# IRQF103C8revC.net
KiCad netlist of a schematic drawn in EAGLE
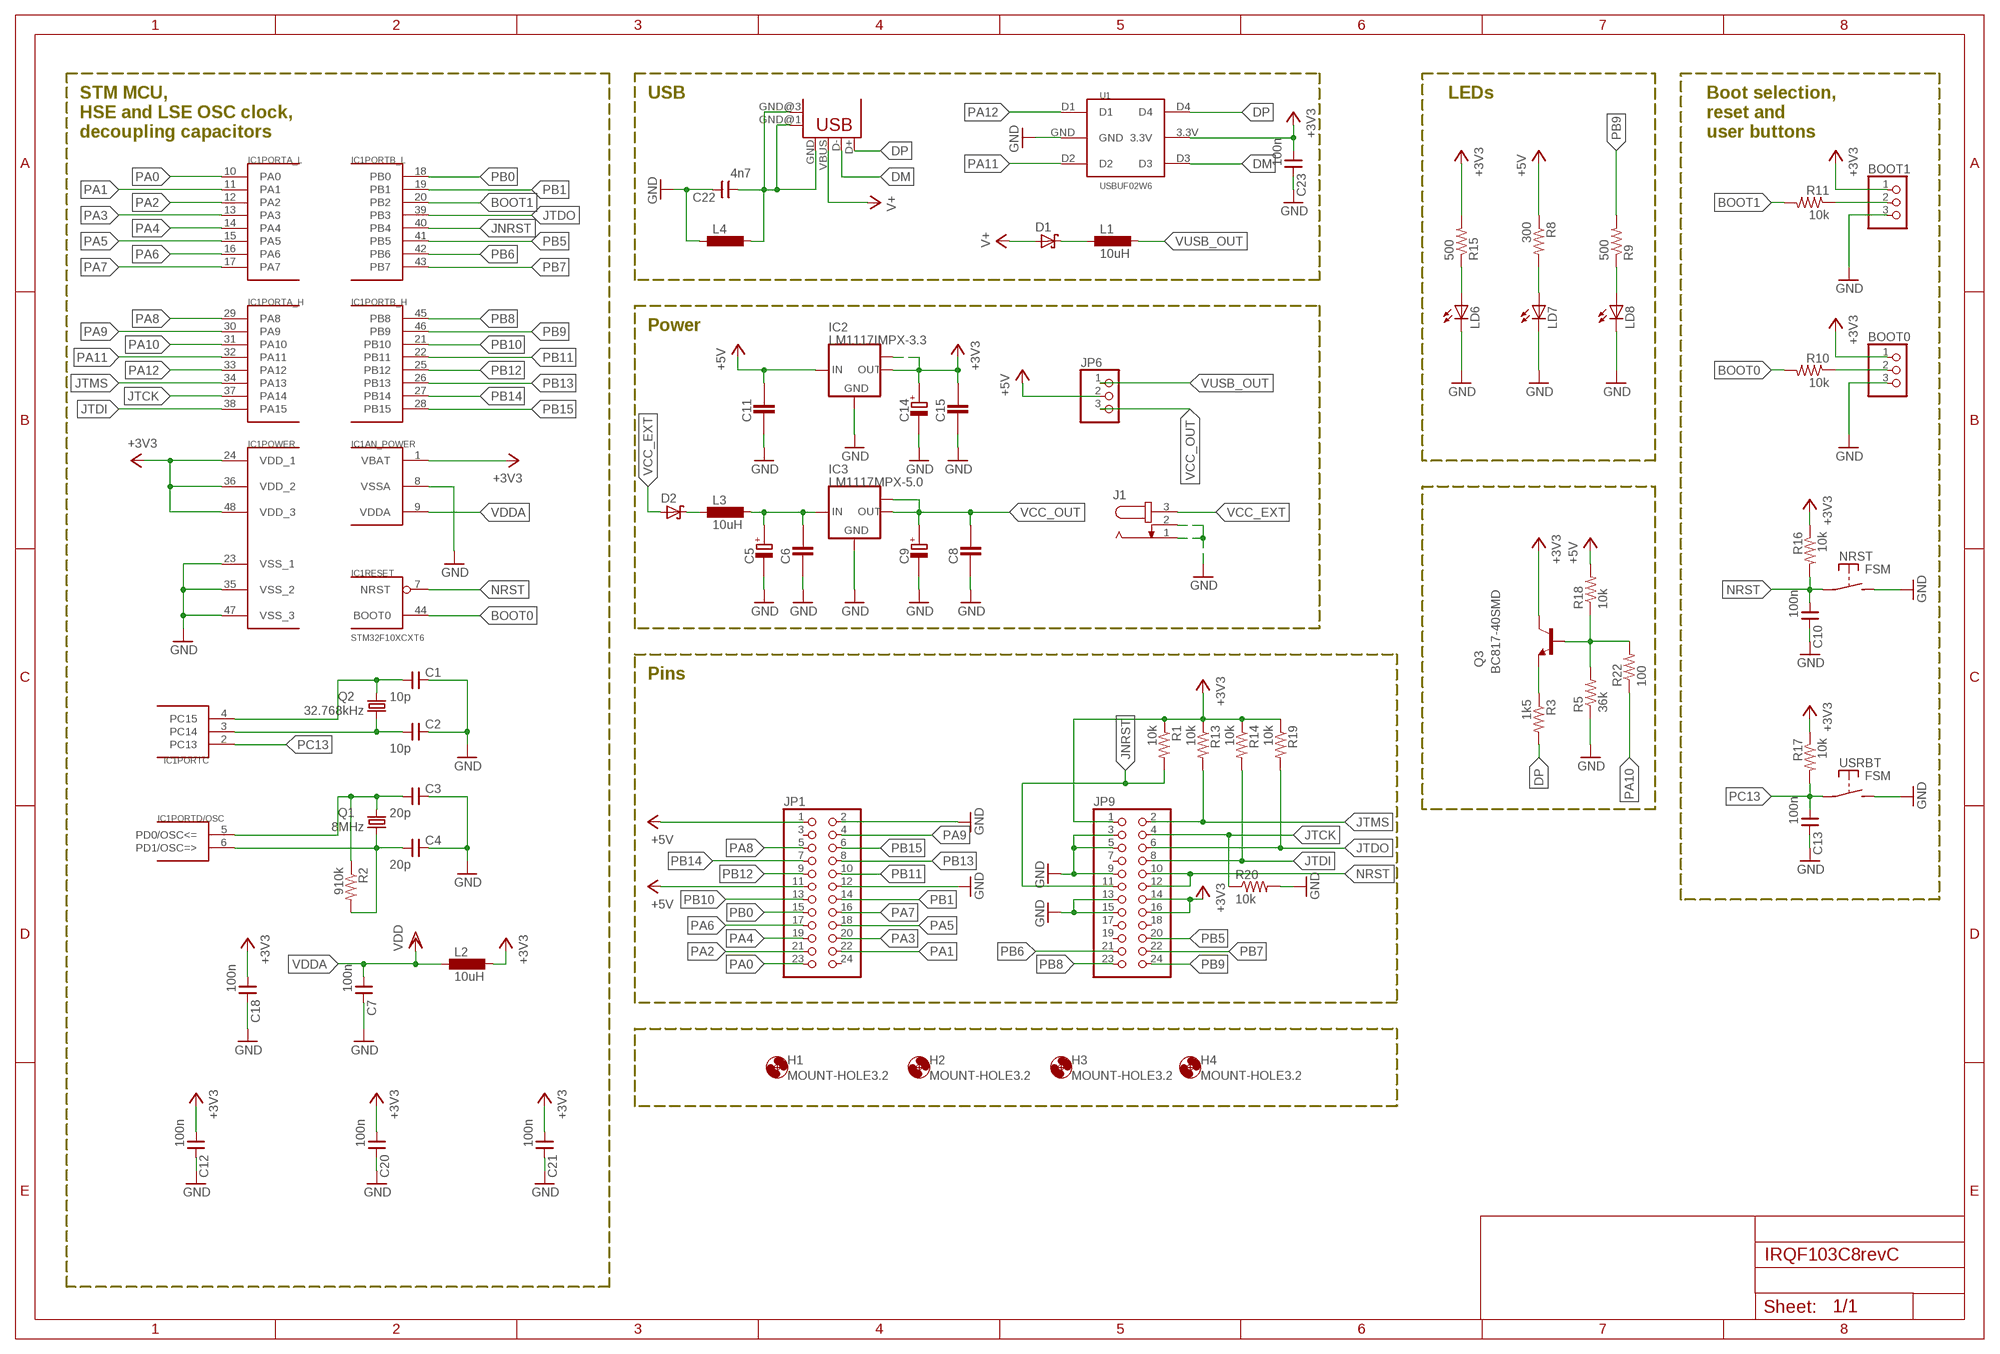
[diagram p0: schematic, sheet 1]

(export (version "E")
  (design (tool "Eeschema 10.0.6"))
  (components
    (comp (ref "BOOT0")
      (value "PINHD-1X3")
      (footprint "eagle-import:1X03")
      (libsource (lib "eagle-import") (part "PINHD-1X3"))
    )
    (comp (ref "BOOT1")
      (value "PINHD-1X3")
      (footprint "eagle-import:1X03")
      (libsource (lib "eagle-import") (part "PINHD-1X3"))
    )
    (comp (ref "C1")
      (value "10p")
      (footprint "eagle-import:0805")
      (libsource (lib "eagle-import") (part "CNP-0805"))
    )
    (comp (ref "C2")
      (value "10p")
      (footprint "eagle-import:0805")
      (libsource (lib "eagle-import") (part "CNP-0805"))
    )
    (comp (ref "C3")
      (value "20p")
      (footprint "eagle-import:0805")
      (libsource (lib "eagle-import") (part "CNP-0805"))
    )
    (comp (ref "C4")
      (value "20p")
      (footprint "eagle-import:0805")
      (libsource (lib "eagle-import") (part "CNP-0805"))
    )
    (comp (ref "C5")
      (value "POLARISED_CASE_B")
      (footprint "eagle-import:CAPAE430X540N")
      (libsource (lib "eagle-import") (part "POLARISED_CASE_B"))
    )
    (comp (ref "C6")
      (value "CAPACITOR_0805")
      (footprint "eagle-import:CAPC2012X145AN")
      (libsource (lib "eagle-import") (part "CAPACITOR_0805"))
    )
    (comp (ref "C7")
      (value "100n")
      (footprint "eagle-import:0805")
      (libsource (lib "eagle-import") (part "CNP-0805"))
    )
    (comp (ref "C8")
      (value "CAPACITOR_0805")
      (footprint "eagle-import:CAPC2012X145AN")
      (libsource (lib "eagle-import") (part "CAPACITOR_0805"))
    )
    (comp (ref "C9")
      (value "POLARISED_CASE_D")
      (footprint "eagle-import:CAPAE660X540N")
      (libsource (lib "eagle-import") (part "POLARISED_CASE_D"))
    )
    (comp (ref "C10")
      (value "100n")
      (footprint "eagle-import:0805")
      (libsource (lib "eagle-import") (part "CNP-0805"))
    )
    (comp (ref "C11")
      (value "CAPACITOR_1206")
      (footprint "eagle-import:CAPC3215X168N")
      (libsource (lib "eagle-import") (part "CAPACITOR_1206"))
    )
    (comp (ref "C12")
      (value "100n")
      (footprint "eagle-import:0805")
      (libsource (lib "eagle-import") (part "CNP-0805"))
    )
    (comp (ref "C13")
      (value "100n")
      (footprint "eagle-import:0805")
      (libsource (lib "eagle-import") (part "CNP-0805"))
    )
    (comp (ref "C14")
      (value "POLARISED_CASE_C")
      (footprint "eagle-import:CAPAE530X540N")
      (libsource (lib "eagle-import") (part "POLARISED_CASE_C"))
    )
    (comp (ref "C15")
      (value "CAPACITOR_0805")
      (footprint "eagle-import:CAPC2012X145AN")
      (libsource (lib "eagle-import") (part "CAPACITOR_0805"))
    )
    (comp (ref "C18")
      (value "100n")
      (footprint "eagle-import:0805")
      (libsource (lib "eagle-import") (part "CNP-0805"))
    )
    (comp (ref "C20")
      (value "100n")
      (footprint "eagle-import:0805")
      (libsource (lib "eagle-import") (part "CNP-0805"))
    )
    (comp (ref "C21")
      (value "100n")
      (footprint "eagle-import:0805")
      (libsource (lib "eagle-import") (part "CNP-0805"))
    )
    (comp (ref "C22")
      (value "4n7")
      (footprint "eagle-import:0805")
      (libsource (lib "eagle-import") (part "CNP-0805"))
    )
    (comp (ref "C23")
      (value "100n")
      (footprint "eagle-import:0805")
      (libsource (lib "eagle-import") (part "CNP-0805"))
    )
    (comp (ref "D1")
      (value "SCHOTTKY_SMA")
      (footprint "eagle-import:DIOM5326X292N")
      (libsource (lib "eagle-import") (part "SCHOTTKY_SMA"))
    )
    (comp (ref "D2")
      (value "SCHOTTKY_SMA")
      (footprint "eagle-import:DIOM5326X292N")
      (libsource (lib "eagle-import") (part "SCHOTTKY_SMA"))
    )
    (comp (ref "H1")
      (value "MOUNT-HOLE3.2")
      (footprint "eagle-import:3,2")
      (libsource (lib "eagle-import") (part "MOUNT-HOLE3.2"))
    )
    (comp (ref "H2")
      (value "MOUNT-HOLE3.2")
      (footprint "eagle-import:3,2")
      (libsource (lib "eagle-import") (part "MOUNT-HOLE3.2"))
    )
    (comp (ref "H3")
      (value "MOUNT-HOLE3.2")
      (footprint "eagle-import:3,2")
      (libsource (lib "eagle-import") (part "MOUNT-HOLE3.2"))
    )
    (comp (ref "H4")
      (value "MOUNT-HOLE3.2")
      (footprint "eagle-import:3,2")
      (libsource (lib "eagle-import") (part "MOUNT-HOLE3.2"))
    )
    (comp (ref "IC1")
      (value "STM32F10XCXT6")
      (footprint "eagle-import:TQFP48")
      (libsource (lib "eagle-import") (part "STM32F10XCXT6"))
    )
    (comp (ref "IC2")
      (value "LM1117IMPX-3.3")
      (footprint "eagle-import:SOT223")
      (libsource (lib "eagle-import") (part "LM1117IMPX-3.3"))
    )
    (comp (ref "IC3")
      (value "LM1117MPX-5.0")
      (footprint "eagle-import:SOT223")
      (libsource (lib "eagle-import") (part "LM1117MPX-5.0"))
    )
    (comp (ref "J1")
      (value "JACK-PLUG1")
      (footprint "eagle-import:SPC4078")
      (libsource (lib "eagle-import") (part "JACK-PLUG1"))
    )
    (comp (ref "JP1")
      (value "PINHD-2X12")
      (footprint "eagle-import:2X12")
      (libsource (lib "eagle-import") (part "PINHD-2X12"))
    )
    (comp (ref "JP6")
      (value "PINHD-1X3")
      (footprint "eagle-import:1X03")
      (libsource (lib "eagle-import") (part "PINHD-1X3"))
    )
    (comp (ref "JP9")
      (value "PINHD-2X12")
      (footprint "eagle-import:2X12")
      (libsource (lib "eagle-import") (part "PINHD-2X12"))
    )
    (comp (ref "L1")
      (value "10uH")
      (footprint "eagle-import:INDC1608X95N")
      (libsource (lib "eagle-import") (part "INDUCTOR_0603"))
    )
    (comp (ref "L2")
      (value "10uH")
      (footprint "eagle-import:INDC1608X95N")
      (libsource (lib "eagle-import") (part "INDUCTOR_0603"))
    )
    (comp (ref "L3")
      (value "10uH")
      (footprint "eagle-import:INDC1608X95N")
      (libsource (lib "eagle-import") (part "INDUCTOR_0603"))
    )
    (comp (ref "L4")
      (value "INDUCTOR_0603")
      (footprint "eagle-import:INDC1608X95N")
      (libsource (lib "eagle-import") (part "INDUCTOR_0603"))
    )
    (comp (ref "LD6")
      (value "LEDCHIPLED_0805")
      (footprint "eagle-import:CHIPLED_0805")
      (libsource (lib "eagle-import") (part "LEDCHIPLED_0805"))
    )
    (comp (ref "LD7")
      (value "LEDCHIPLED_0805")
      (footprint "eagle-import:CHIPLED_0805")
      (libsource (lib "eagle-import") (part "LEDCHIPLED_0805"))
    )
    (comp (ref "LD8")
      (value "LEDCHIPLED_0805")
      (footprint "eagle-import:CHIPLED_0805")
      (libsource (lib "eagle-import") (part "LEDCHIPLED_0805"))
    )
    (comp (ref "NRST")
      (value "FSM")
      (footprint "eagle-import:FSM")
      (libsource (lib "eagle-import") (part "FSM"))
    )
    (comp (ref "Q1")
      (value "8MHz")
      (footprint "eagle-import:HC49_S")
      (libsource (lib "eagle-import") (part "CRYTALHC49S"))
    )
    (comp (ref "Q2")
      (value "32.768kHz")
      (footprint "eagle-import:TC26H")
      (libsource (lib "eagle-import") (part "CRYTALTC26H"))
    )
    (comp (ref "Q3")
      (value "BC817-40SMD")
      (footprint "eagle-import:SOT23-BEC")
      (libsource (lib "eagle-import") (part "BC817SMD-40"))
    )
    (comp (ref "R1")
      (value "10k")
      (footprint "eagle-import:M0805")
      (libsource (lib "eagle-import") (part "R-US_M0805"))
    )
    (comp (ref "R2")
      (value "910k")
      (footprint "eagle-import:M0805")
      (libsource (lib "eagle-import") (part "R-US_M0805"))
    )
    (comp (ref "R3")
      (value "1k5")
      (footprint "eagle-import:M0805")
      (libsource (lib "eagle-import") (part "R-US_M0805"))
    )
    (comp (ref "R5")
      (value "36k")
      (footprint "eagle-import:M0805")
      (libsource (lib "eagle-import") (part "R-US_M0805"))
    )
    (comp (ref "R8")
      (value "300")
      (footprint "eagle-import:M0805")
      (libsource (lib "eagle-import") (part "R-US_M0805"))
    )
    (comp (ref "R9")
      (value "500")
      (footprint "eagle-import:M0805")
      (libsource (lib "eagle-import") (part "R-US_M0805"))
    )
    (comp (ref "R10")
      (value "10k")
      (footprint "eagle-import:M0805")
      (libsource (lib "eagle-import") (part "R-US_M0805"))
    )
    (comp (ref "R11")
      (value "10k")
      (footprint "eagle-import:M0805")
      (libsource (lib "eagle-import") (part "R-US_M0805"))
    )
    (comp (ref "R13")
      (value "10k")
      (footprint "eagle-import:M0805")
      (libsource (lib "eagle-import") (part "R-US_M0805"))
    )
    (comp (ref "R14")
      (value "10k")
      (footprint "eagle-import:M0805")
      (libsource (lib "eagle-import") (part "R-US_M0805"))
    )
    (comp (ref "R15")
      (value "500")
      (footprint "eagle-import:M0805")
      (libsource (lib "eagle-import") (part "R-US_M0805"))
    )
    (comp (ref "R16")
      (value "10k")
      (footprint "eagle-import:M0805")
      (libsource (lib "eagle-import") (part "R-US_M0805"))
    )
    (comp (ref "R17")
      (value "10k")
      (footprint "eagle-import:M0805")
      (libsource (lib "eagle-import") (part "R-US_M0805"))
    )
    (comp (ref "R18")
      (value "10k")
      (footprint "eagle-import:M0805")
      (libsource (lib "eagle-import") (part "R-US_M0805"))
    )
    (comp (ref "R19")
      (value "10k")
      (footprint "eagle-import:M0805")
      (libsource (lib "eagle-import") (part "R-US_M0805"))
    )
    (comp (ref "R20")
      (value "10k")
      (footprint "eagle-import:M0805")
      (libsource (lib "eagle-import") (part "R-US_M0805"))
    )
    (comp (ref "R22")
      (value "100")
      (footprint "eagle-import:M0805")
      (libsource (lib "eagle-import") (part "R-US_M0805"))
    )
    (comp (ref "U1")
      (value "USBUF02W6")
      (footprint "eagle-import:SOT23-6L")
      (libsource (lib "eagle-import") (part "USBUF02W6"))
    )
    (comp (ref "USB1")
      (value "USB-MB-S")
      (footprint "eagle-import:USB-MB-S")
      (libsource (lib "eagle-import") (part "USB-MB-S"))
    )
    (comp (ref "USRBT")
      (value "FSM")
      (footprint "eagle-import:FSM")
      (libsource (lib "eagle-import") (part "FSM"))
    )
  )
  (nets
    (net (code "1") (name "+3V3") (class "Default")
      (node (ref "BOOT0") (pin "1") (pinfunction "1_1") (pintype "passive"))
      (node (ref "BOOT1") (pin "1") (pinfunction "1_1") (pintype "passive"))
      (node (ref "C12") (pin "1") (pinfunction "1_1") (pintype "passive"))
      (node (ref "C14") (pin "+") (pinfunction "+_+") (pintype "passive"))
      (node (ref "C15") (pin "2") (pinfunction "2_2") (pintype "passive"))
      (node (ref "C18") (pin "1") (pinfunction "1_1") (pintype "passive"))
      (node (ref "C20") (pin "1") (pinfunction "1_1") (pintype "passive"))
      (node (ref "C21") (pin "1") (pinfunction "1_1") (pintype "passive"))
      (node (ref "C23") (pin "1") (pinfunction "1_1") (pintype "passive"))
      (node (ref "IC1") (pin "1") (pinfunction "VBAT_1") (pintype "power_in"))
      (node (ref "IC1") (pin "24") (pinfunction "VDD_1_24") (pintype "power_in"))
      (node (ref "IC1") (pin "36") (pinfunction "VDD_2_36") (pintype "power_in"))
      (node (ref "IC1") (pin "48") (pinfunction "VDD_3_48") (pintype "power_in"))
      (node (ref "IC2") (pin "2") (pinfunction "OUT_2") (pintype "passive"))
      (node (ref "IC2") (pin "TAB") (pinfunction "OUT1_TAB") (pintype "passive"))
      (node (ref "JP9") (pin "1") (pinfunction "1_1") (pintype "passive"))
      (node (ref "JP9") (pin "14") (pinfunction "14_14") (pintype "passive"))
      (node (ref "JP9") (pin "16") (pinfunction "16_16") (pintype "passive"))
      (node (ref "L2") (pin "2") (pinfunction "2_2") (pintype "passive"))
      (node (ref "Q3") (pin "C") (pinfunction "C_C") (pintype "passive"))
      (node (ref "R1") (pin "1") (pinfunction "1_1") (pintype "passive"))
      (node (ref "R13") (pin "1") (pinfunction "1_1") (pintype "passive"))
      (node (ref "R14") (pin "1") (pinfunction "1_1") (pintype "passive"))
      (node (ref "R15") (pin "2") (pinfunction "2_2") (pintype "passive"))
      (node (ref "R16") (pin "1") (pinfunction "1_1") (pintype "passive"))
      (node (ref "R17") (pin "1") (pinfunction "1_1") (pintype "passive"))
      (node (ref "R19") (pin "1") (pinfunction "1_1") (pintype "passive"))
      (node (ref "U1") (pin "3.3V") (pinfunction "3.3V_3.3V") (pintype "bidirectional"))
    )
    (net (code "2") (name "+5V") (class "Default")
      (node (ref "C11") (pin "2") (pinfunction "2_2") (pintype "passive"))
      (node (ref "IC2") (pin "3") (pinfunction "IN_3") (pintype "input"))
      (node (ref "JP1") (pin "1") (pinfunction "1_1") (pintype "passive"))
      (node (ref "JP1") (pin "11") (pinfunction "11_11") (pintype "passive"))
      (node (ref "JP6") (pin "2") (pinfunction "2_2") (pintype "passive"))
      (node (ref "R18") (pin "2") (pinfunction "2_2") (pintype "passive"))
      (node (ref "R8") (pin "1") (pinfunction "1_1") (pintype "passive"))
    )
    (net (code "3") (name "BOOT0") (class "Default")
      (node (ref "IC1") (pin "44") (pinfunction "BOOT0_44") (pintype "input"))
      (node (ref "R10") (pin "2") (pinfunction "2_2") (pintype "passive"))
    )
    (net (code "4") (name "BOOT1") (class "Default")
      (node (ref "IC1") (pin "20") (pinfunction "PB2_20") (pintype "bidirectional"))
      (node (ref "R11") (pin "2") (pinfunction "2_2") (pintype "passive"))
    )
    (net (code "5") (name "DM") (class "Default")
      (node (ref "U1") (pin "D3") (pinfunction "D3_D3") (pintype "bidirectional"))
      (node (ref "USB1") (pin "D-") (pinfunction "D-_D-") (pintype "bidirectional"))
    )
    (net (code "6") (name "DP") (class "Default")
      (node (ref "R3") (pin "2") (pinfunction "2_2") (pintype "passive"))
      (node (ref "U1") (pin "D4") (pinfunction "D4_D4") (pintype "bidirectional"))
      (node (ref "USB1") (pin "D+") (pinfunction "D+_D+") (pintype "bidirectional"))
    )
    (net (code "7") (name "GND") (class "Default")
      (node (ref "BOOT0") (pin "3") (pinfunction "3_3") (pintype "passive"))
      (node (ref "BOOT1") (pin "3") (pinfunction "3_3") (pintype "passive"))
      (node (ref "C1") (pin "2") (pinfunction "2_2") (pintype "passive"))
      (node (ref "C10") (pin "2") (pinfunction "2_2") (pintype "passive"))
      (node (ref "C11") (pin "1") (pinfunction "1_1") (pintype "passive"))
      (node (ref "C12") (pin "2") (pinfunction "2_2") (pintype "passive"))
      (node (ref "C13") (pin "2") (pinfunction "2_2") (pintype "passive"))
      (node (ref "C14") (pin "-") (pinfunction "-_-") (pintype "passive"))
      (node (ref "C15") (pin "1") (pinfunction "1_1") (pintype "passive"))
      (node (ref "C18") (pin "2") (pinfunction "2_2") (pintype "passive"))
      (node (ref "C2") (pin "2") (pinfunction "2_2") (pintype "passive"))
      (node (ref "C20") (pin "2") (pinfunction "2_2") (pintype "passive"))
      (node (ref "C21") (pin "2") (pinfunction "2_2") (pintype "passive"))
      (node (ref "C22") (pin "2") (pinfunction "2_2") (pintype "passive"))
      (node (ref "C23") (pin "2") (pinfunction "2_2") (pintype "passive"))
      (node (ref "C3") (pin "2") (pinfunction "2_2") (pintype "passive"))
      (node (ref "C4") (pin "2") (pinfunction "2_2") (pintype "passive"))
      (node (ref "C5") (pin "-") (pinfunction "-_-") (pintype "passive"))
      (node (ref "C6") (pin "1") (pinfunction "1_1") (pintype "passive"))
      (node (ref "C7") (pin "2") (pinfunction "2_2") (pintype "passive"))
      (node (ref "C8") (pin "1") (pinfunction "1_1") (pintype "passive"))
      (node (ref "C9") (pin "-") (pinfunction "-_-") (pintype "passive"))
      (node (ref "IC1") (pin "23") (pinfunction "VSS_1_23") (pintype "power_in"))
      (node (ref "IC1") (pin "35") (pinfunction "VSS_2_35") (pintype "power_in"))
      (node (ref "IC1") (pin "47") (pinfunction "VSS_3_47") (pintype "power_in"))
      (node (ref "IC1") (pin "8") (pinfunction "VSSA_8") (pintype "power_in"))
      (node (ref "IC2") (pin "1") (pinfunction "GND_1") (pintype "input"))
      (node (ref "IC3") (pin "1") (pinfunction "GND_1") (pintype "input"))
      (node (ref "J1") (pin "1") (pinfunction "1_1") (pintype "passive"))
      (node (ref "J1") (pin "2") (pinfunction "2_2") (pintype "passive"))
      (node (ref "JP1") (pin "12") (pinfunction "12_12") (pintype "passive"))
      (node (ref "JP1") (pin "2") (pinfunction "2_2") (pintype "passive"))
      (node (ref "JP9") (pin "13") (pinfunction "13_13") (pintype "passive"))
      (node (ref "JP9") (pin "15") (pinfunction "15_15") (pintype "passive"))
      (node (ref "JP9") (pin "3") (pinfunction "3_3") (pintype "passive"))
      (node (ref "JP9") (pin "5") (pinfunction "5_5") (pintype "passive"))
      (node (ref "JP9") (pin "9") (pinfunction "9_9") (pintype "passive"))
      (node (ref "L4") (pin "1") (pinfunction "1_1") (pintype "passive"))
      (node (ref "LD6") (pin "C") (pinfunction "C_C") (pintype "passive"))
      (node (ref "LD7") (pin "C") (pinfunction "C_C") (pintype "passive"))
      (node (ref "LD8") (pin "C") (pinfunction "C_C") (pintype "passive"))
      (node (ref "NRST") (pin "P$2") (pinfunction "S_P$2") (pintype "passive"))
      (node (ref "R20") (pin "2") (pinfunction "2_2") (pintype "passive"))
      (node (ref "R5") (pin "1") (pinfunction "1_1") (pintype "passive"))
      (node (ref "U1") (pin "GND") (pinfunction "GND_GND") (pintype "bidirectional"))
      (node (ref "USRBT") (pin "P$2") (pinfunction "S_P$2") (pintype "passive"))
    )
    (net (code "8") (name "JNRST") (class "Default")
      (node (ref "IC1") (pin "40") (pinfunction "PB4_40") (pintype "bidirectional"))
      (node (ref "JP9") (pin "11") (pinfunction "11_11") (pintype "passive"))
      (node (ref "R1") (pin "2") (pinfunction "2_2") (pintype "passive"))
    )
    (net (code "9") (name "JTCK") (class "Default")
      (node (ref "IC1") (pin "37") (pinfunction "PA14_37") (pintype "bidirectional"))
      (node (ref "JP9") (pin "4") (pinfunction "4_4") (pintype "passive"))
      (node (ref "R20") (pin "1") (pinfunction "1_1") (pintype "passive"))
    )
    (net (code "10") (name "JTDI") (class "Default")
      (node (ref "IC1") (pin "38") (pinfunction "PA15_38") (pintype "bidirectional"))
      (node (ref "JP9") (pin "8") (pinfunction "8_8") (pintype "passive"))
      (node (ref "R14") (pin "2") (pinfunction "2_2") (pintype "passive"))
    )
    (net (code "11") (name "JTDO") (class "Default")
      (node (ref "IC1") (pin "39") (pinfunction "PB3_39") (pintype "bidirectional"))
      (node (ref "JP9") (pin "6") (pinfunction "6_6") (pintype "passive"))
      (node (ref "R19") (pin "2") (pinfunction "2_2") (pintype "passive"))
    )
    (net (code "12") (name "JTMS") (class "Default")
      (node (ref "IC1") (pin "34") (pinfunction "PA13_34") (pintype "bidirectional"))
      (node (ref "JP9") (pin "2") (pinfunction "2_2") (pintype "passive"))
      (node (ref "R13") (pin "2") (pinfunction "2_2") (pintype "passive"))
    )
    (net (code "13") (name "NRST") (class "Default")
      (node (ref "C10") (pin "1") (pinfunction "1_1") (pintype "passive"))
      (node (ref "IC1") (pin "7") (pinfunction "NRST_7") (pintype "input"))
      (node (ref "JP9") (pin "10") (pinfunction "10_10") (pintype "passive"))
      (node (ref "JP9") (pin "12") (pinfunction "12_12") (pintype "passive"))
      (node (ref "NRST") (pin "P$1") (pinfunction "P_P$1") (pintype "passive"))
      (node (ref "R16") (pin "2") (pinfunction "2_2") (pintype "passive"))
    )
    (net (code "14") (name "Net-(BOOT0-Pad2)") (class "Default")
      (node (ref "BOOT0") (pin "2") (pinfunction "2_2") (pintype "passive"))
      (node (ref "R10") (pin "1") (pinfunction "1_1") (pintype "passive"))
    )
    (net (code "15") (name "Net-(BOOT1-Pad2)") (class "Default")
      (node (ref "BOOT1") (pin "2") (pinfunction "2_2") (pintype "passive"))
      (node (ref "R11") (pin "1") (pinfunction "1_1") (pintype "passive"))
    )
    (net (code "16") (name "Net-(C22-Pad1)") (class "Default")
      (node (ref "C22") (pin "1") (pinfunction "1_1") (pintype "passive"))
      (node (ref "L4") (pin "2") (pinfunction "2_2") (pintype "passive"))
      (node (ref "USB1") (pin "GND") (pinfunction "GND_GND") (pintype "bidirectional"))
      (node (ref "USB1") (pin "GND@1") (pinfunction "GND_GND@1") (pintype "bidirectional"))
      (node (ref "USB1") (pin "GND@3") (pinfunction "GND_GND@3") (pintype "bidirectional"))
    )
    (net (code "17") (name "Net-(D1-PadK)") (class "Default")
      (node (ref "D1") (pin "K") (pinfunction "K_K") (pintype "passive"))
      (node (ref "L1") (pin "1") (pinfunction "1_1") (pintype "passive"))
    )
    (net (code "18") (name "Net-(D2-PadK)") (class "Default")
      (node (ref "D2") (pin "K") (pinfunction "K_K") (pintype "passive"))
      (node (ref "L3") (pin "1") (pinfunction "1_1") (pintype "passive"))
    )
    (net (code "19") (name "Net-(IC1F-PC14)") (class "Default")
      (node (ref "C2") (pin "1") (pinfunction "1_1") (pintype "passive"))
      (node (ref "IC1") (pin "3") (pinfunction "PC14_3") (pintype "bidirectional"))
      (node (ref "Q2") (pin "1") (pinfunction "1_1") (pintype "passive"))
    )
    (net (code "20") (name "Net-(IC1F-PC15)") (class "Default")
      (node (ref "C1") (pin "1") (pinfunction "1_1") (pintype "passive"))
      (node (ref "IC1") (pin "4") (pinfunction "PC15_4") (pintype "bidirectional"))
      (node (ref "Q2") (pin "2") (pinfunction "2_2") (pintype "passive"))
    )
    (net (code "21") (name "Net-(IC1G-PD0{slash}OSC<=)") (class "Default")
      (node (ref "C3") (pin "1") (pinfunction "1_1") (pintype "passive"))
      (node (ref "IC1") (pin "5") (pinfunction "PD0/OSC<=_5") (pintype "bidirectional"))
      (node (ref "Q1") (pin "2") (pinfunction "2_2") (pintype "passive"))
      (node (ref "R2") (pin "1") (pinfunction "1_1") (pintype "passive"))
    )
    (net (code "22") (name "Net-(IC1G-PD1{slash}OSC=>)") (class "Default")
      (node (ref "C4") (pin "1") (pinfunction "1_1") (pintype "passive"))
      (node (ref "IC1") (pin "6") (pinfunction "PD1/OSC=>_6") (pintype "bidirectional"))
      (node (ref "Q1") (pin "1") (pinfunction "1_1") (pintype "passive"))
      (node (ref "R2") (pin "2") (pinfunction "2_2") (pintype "passive"))
    )
    (net (code "23") (name "Net-(IC3-IN)") (class "Default")
      (node (ref "C5") (pin "+") (pinfunction "+_+") (pintype "passive"))
      (node (ref "C6") (pin "2") (pinfunction "2_2") (pintype "passive"))
      (node (ref "IC3") (pin "3") (pinfunction "IN_3") (pintype "input"))
      (node (ref "L3") (pin "2") (pinfunction "2_2") (pintype "passive"))
    )
    (net (code "24") (name "Net-(LD6-PadA)") (class "Default")
      (node (ref "LD6") (pin "A") (pinfunction "A_A") (pintype "passive"))
      (node (ref "R15") (pin "1") (pinfunction "1_1") (pintype "passive"))
    )
    (net (code "25") (name "Net-(LD7-PadA)") (class "Default")
      (node (ref "LD7") (pin "A") (pinfunction "A_A") (pintype "passive"))
      (node (ref "R8") (pin "2") (pinfunction "2_2") (pintype "passive"))
    )
    (net (code "26") (name "Net-(LD8-PadA)") (class "Default")
      (node (ref "LD8") (pin "A") (pinfunction "A_A") (pintype "passive"))
      (node (ref "R9") (pin "1") (pinfunction "1_1") (pintype "passive"))
    )
    (net (code "27") (name "Net-(Q3-PadB)") (class "Default")
      (node (ref "Q3") (pin "B") (pinfunction "B_B") (pintype "passive"))
      (node (ref "R18") (pin "1") (pinfunction "1_1") (pintype "passive"))
      (node (ref "R22") (pin "2") (pinfunction "2_2") (pintype "passive"))
      (node (ref "R5") (pin "2") (pinfunction "2_2") (pintype "passive"))
    )
    (net (code "28") (name "Net-(Q3-PadE)") (class "Default")
      (node (ref "Q3") (pin "E") (pinfunction "E_E") (pintype "passive"))
      (node (ref "R3") (pin "1") (pinfunction "1_1") (pintype "passive"))
    )
    (net (code "29") (name "PA0") (class "Default")
      (node (ref "IC1") (pin "10") (pinfunction "PA0_10") (pintype "bidirectional"))
      (node (ref "JP1") (pin "23") (pinfunction "23_23") (pintype "passive"))
    )
    (net (code "30") (name "PA1") (class "Default")
      (node (ref "IC1") (pin "11") (pinfunction "PA1_11") (pintype "bidirectional"))
      (node (ref "JP1") (pin "22") (pinfunction "22_22") (pintype "passive"))
    )
    (net (code "31") (name "PA2") (class "Default")
      (node (ref "IC1") (pin "12") (pinfunction "PA2_12") (pintype "bidirectional"))
      (node (ref "JP1") (pin "21") (pinfunction "21_21") (pintype "passive"))
    )
    (net (code "32") (name "PA3") (class "Default")
      (node (ref "IC1") (pin "13") (pinfunction "PA3_13") (pintype "bidirectional"))
      (node (ref "JP1") (pin "20") (pinfunction "20_20") (pintype "passive"))
    )
    (net (code "33") (name "PA4") (class "Default")
      (node (ref "IC1") (pin "14") (pinfunction "PA4_14") (pintype "bidirectional"))
      (node (ref "JP1") (pin "19") (pinfunction "19_19") (pintype "passive"))
    )
    (net (code "34") (name "PA5") (class "Default")
      (node (ref "IC1") (pin "15") (pinfunction "PA5_15") (pintype "bidirectional"))
      (node (ref "JP1") (pin "18") (pinfunction "18_18") (pintype "passive"))
    )
    (net (code "35") (name "PA6") (class "Default")
      (node (ref "IC1") (pin "16") (pinfunction "PA6_16") (pintype "bidirectional"))
      (node (ref "JP1") (pin "17") (pinfunction "17_17") (pintype "passive"))
    )
    (net (code "36") (name "PA7") (class "Default")
      (node (ref "IC1") (pin "17") (pinfunction "PA7_17") (pintype "bidirectional"))
      (node (ref "JP1") (pin "16") (pinfunction "16_16") (pintype "passive"))
    )
    (net (code "37") (name "PA8") (class "Default")
      (node (ref "IC1") (pin "29") (pinfunction "PA8_29") (pintype "bidirectional"))
      (node (ref "JP1") (pin "5") (pinfunction "5_5") (pintype "passive"))
    )
    (net (code "38") (name "PA9") (class "Default")
      (node (ref "IC1") (pin "30") (pinfunction "PA9_30") (pintype "bidirectional"))
      (node (ref "JP1") (pin "4") (pinfunction "4_4") (pintype "passive"))
    )
    (net (code "39") (name "PA10") (class "Default")
      (node (ref "IC1") (pin "31") (pinfunction "PA10_31") (pintype "bidirectional"))
      (node (ref "R22") (pin "1") (pinfunction "1_1") (pintype "passive"))
    )
    (net (code "40") (name "PA11") (class "Default")
      (node (ref "IC1") (pin "32") (pinfunction "PA11_32") (pintype "bidirectional"))
      (node (ref "U1") (pin "D2") (pinfunction "D2_D2") (pintype "bidirectional"))
    )
    (net (code "41") (name "PA12") (class "Default")
      (node (ref "IC1") (pin "33") (pinfunction "PA12_33") (pintype "bidirectional"))
      (node (ref "U1") (pin "D1") (pinfunction "D1_D1") (pintype "bidirectional"))
    )
    (net (code "42") (name "PB0") (class "Default")
      (node (ref "IC1") (pin "18") (pinfunction "PB0_18") (pintype "bidirectional"))
      (node (ref "JP1") (pin "15") (pinfunction "15_15") (pintype "passive"))
    )
    (net (code "43") (name "PB1") (class "Default")
      (node (ref "IC1") (pin "19") (pinfunction "PB1_19") (pintype "bidirectional"))
      (node (ref "JP1") (pin "14") (pinfunction "14_14") (pintype "passive"))
    )
    (net (code "44") (name "PB5") (class "Default")
      (node (ref "IC1") (pin "41") (pinfunction "PB5_41") (pintype "bidirectional"))
      (node (ref "JP9") (pin "20") (pinfunction "20_20") (pintype "passive"))
    )
    (net (code "45") (name "PB6") (class "Default")
      (node (ref "IC1") (pin "42") (pinfunction "PB6_42") (pintype "bidirectional"))
      (node (ref "JP9") (pin "21") (pinfunction "21_21") (pintype "passive"))
    )
    (net (code "46") (name "PB7") (class "Default")
      (node (ref "IC1") (pin "43") (pinfunction "PB7_43") (pintype "bidirectional"))
      (node (ref "JP9") (pin "22") (pinfunction "22_22") (pintype "passive"))
    )
    (net (code "47") (name "PB8") (class "Default")
      (node (ref "IC1") (pin "45") (pinfunction "PB8_45") (pintype "bidirectional"))
      (node (ref "JP9") (pin "23") (pinfunction "23_23") (pintype "passive"))
    )
    (net (code "48") (name "PB9") (class "Default")
      (node (ref "IC1") (pin "46") (pinfunction "PB9_46") (pintype "bidirectional"))
      (node (ref "JP9") (pin "24") (pinfunction "24_24") (pintype "passive"))
      (node (ref "R9") (pin "2") (pinfunction "2_2") (pintype "passive"))
    )
    (net (code "49") (name "PB10") (class "Default")
      (node (ref "IC1") (pin "21") (pinfunction "PB10_21") (pintype "bidirectional"))
      (node (ref "JP1") (pin "13") (pinfunction "13_13") (pintype "passive"))
    )
    (net (code "50") (name "PB11") (class "Default")
      (node (ref "IC1") (pin "22") (pinfunction "PB11_22") (pintype "bidirectional"))
      (node (ref "JP1") (pin "10") (pinfunction "10_10") (pintype "passive"))
    )
    (net (code "51") (name "PB12") (class "Default")
      (node (ref "IC1") (pin "25") (pinfunction "PB12_25") (pintype "bidirectional"))
      (node (ref "JP1") (pin "9") (pinfunction "9_9") (pintype "passive"))
    )
    (net (code "52") (name "PB13") (class "Default")
      (node (ref "IC1") (pin "26") (pinfunction "PB13_26") (pintype "bidirectional"))
      (node (ref "JP1") (pin "8") (pinfunction "8_8") (pintype "passive"))
    )
    (net (code "53") (name "PB14") (class "Default")
      (node (ref "IC1") (pin "27") (pinfunction "PB14_27") (pintype "bidirectional"))
      (node (ref "JP1") (pin "7") (pinfunction "7_7") (pintype "passive"))
    )
    (net (code "54") (name "PB15") (class "Default")
      (node (ref "IC1") (pin "28") (pinfunction "PB15_28") (pintype "bidirectional"))
      (node (ref "JP1") (pin "6") (pinfunction "6_6") (pintype "passive"))
    )
    (net (code "55") (name "PC13") (class "Default")
      (node (ref "C13") (pin "1") (pinfunction "1_1") (pintype "passive"))
      (node (ref "IC1") (pin "2") (pinfunction "PC13_2") (pintype "bidirectional"))
      (node (ref "R17") (pin "2") (pinfunction "2_2") (pintype "passive"))
      (node (ref "USRBT") (pin "P$1") (pinfunction "P_P$1") (pintype "passive"))
    )
    (net (code "56") (name "V+") (class "Default")
      (node (ref "D1") (pin "A") (pinfunction "A_A") (pintype "passive"))
      (node (ref "USB1") (pin "VBUS") (pinfunction "VBUS_VBUS") (pintype "bidirectional"))
    )
    (net (code "57") (name "VCC_EXT") (class "Default")
      (node (ref "D2") (pin "A") (pinfunction "A_A") (pintype "passive"))
      (node (ref "J1") (pin "3") (pinfunction "3_3") (pintype "passive"))
    )
    (net (code "58") (name "VCC_OUT") (class "Default")
      (node (ref "C8") (pin "2") (pinfunction "2_2") (pintype "passive"))
      (node (ref "C9") (pin "+") (pinfunction "+_+") (pintype "passive"))
      (node (ref "IC3") (pin "2") (pinfunction "OUT_2") (pintype "passive"))
      (node (ref "IC3") (pin "TAB") (pinfunction "OUT1_TAB") (pintype "passive"))
      (node (ref "JP6") (pin "3") (pinfunction "3_3") (pintype "passive"))
    )
    (net (code "59") (name "VDDA") (class "Default")
      (node (ref "C7") (pin "1") (pinfunction "1_1") (pintype "passive"))
      (node (ref "IC1") (pin "9") (pinfunction "VDDA_9") (pintype "power_in"))
      (node (ref "L2") (pin "1") (pinfunction "1_1") (pintype "passive"))
    )
    (net (code "60") (name "VUSB_OUT") (class "Default")
      (node (ref "JP6") (pin "1") (pinfunction "1_1") (pintype "passive"))
      (node (ref "L1") (pin "2") (pinfunction "2_2") (pintype "passive"))
    )
    (net (code "61") (name "unconnected-(JP1-Pad3)") (class "Default")
      (node (ref "JP1") (pin "3") (pinfunction "3_3") (pintype "passive"))
    )
    (net (code "62") (name "unconnected-(JP1-Pad24)") (class "Default")
      (node (ref "JP1") (pin "24") (pinfunction "24_24") (pintype "passive"))
    )
    (net (code "63") (name "unconnected-(JP9-Pad7)") (class "Default")
      (node (ref "JP9") (pin "7") (pinfunction "7_7") (pintype "passive"))
    )
    (net (code "64") (name "unconnected-(JP9-Pad17)") (class "Default")
      (node (ref "JP9") (pin "17") (pinfunction "17_17") (pintype "passive"))
    )
    (net (code "65") (name "unconnected-(JP9-Pad18)") (class "Default")
      (node (ref "JP9") (pin "18") (pinfunction "18_18") (pintype "passive"))
    )
    (net (code "66") (name "unconnected-(JP9-Pad19)") (class "Default")
      (node (ref "JP9") (pin "19") (pinfunction "19_19") (pintype "passive"))
    )
  )
)
